# lcd.net
KiCad netlist of a schematic drawn in EAGLE
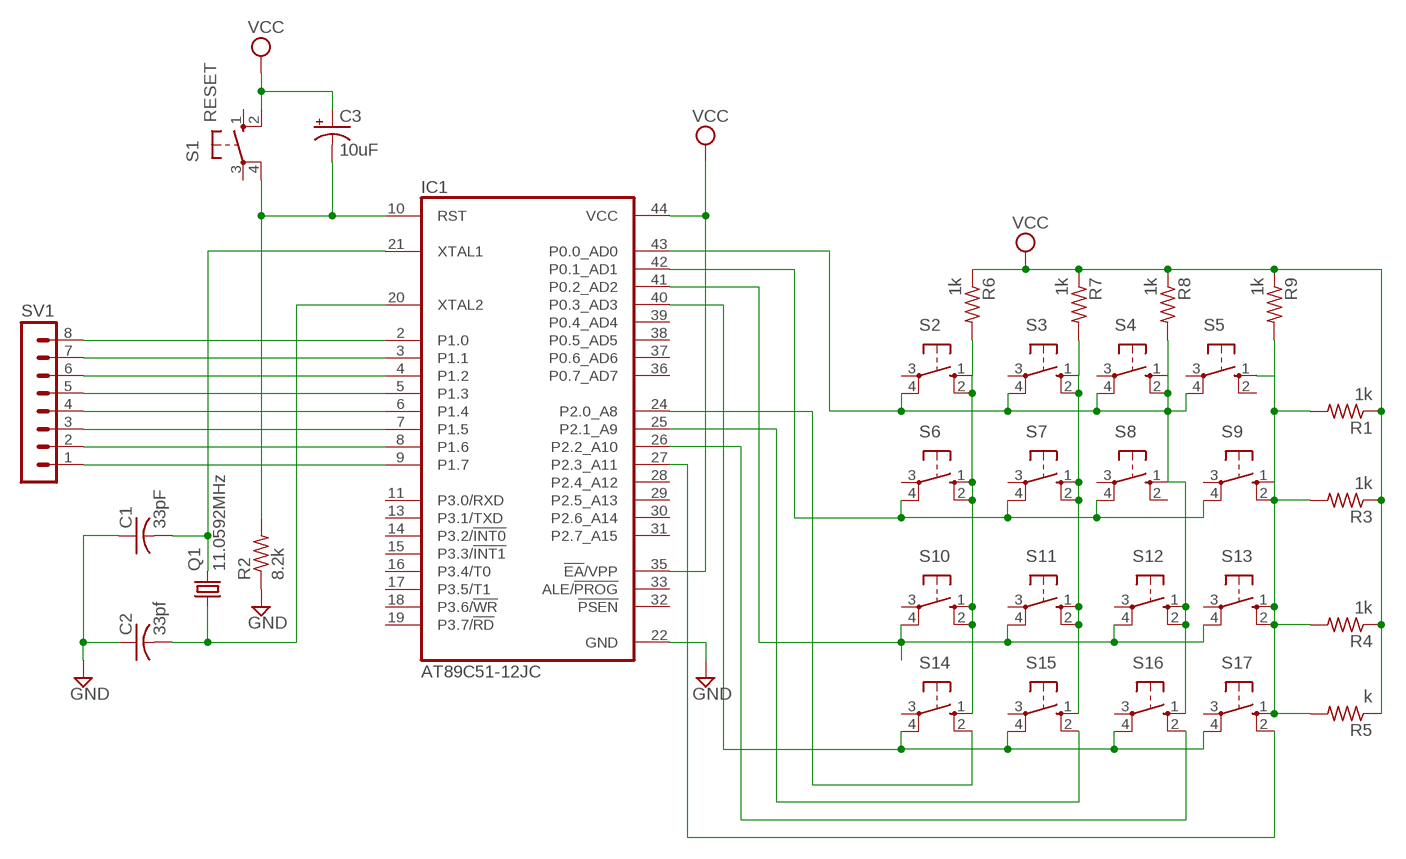
[diagram p0: schematic, sheet 1]

(export (version "E")
  (design (tool "Eeschema 10.0.6"))
  (components
    (comp (ref "C1")
      (value "33pF")
      (footprint "eagle-import:C025-025X050")
      (libsource (lib "eagle-import") (part "C-US025-025X050"))
    )
    (comp (ref "C2")
      (value "33pf")
      (footprint "eagle-import:C025-025X050")
      (libsource (lib "eagle-import") (part "C-US025-025X050"))
    )
    (comp (ref "C3")
      (value "10uF")
      (footprint "eagle-import:E2,5-5")
      (libsource (lib "eagle-import") (part "CPOL-USE2.5-5"))
    )
    (comp (ref "IC1")
      (value "AT89C51-12JC")
      (footprint "eagle-import:PLCC44")
      (fields (field (name "MPN") "AT89C51ED2-SLSUM"))
      (libsource (lib "eagle-import") (part "AT89C51-JC12"))
    )
    (comp (ref "Q1")
      (value "11.0592MHz")
      (footprint "eagle-import:TC26H")
      (libsource (lib "eagle-import") (part "CRYSTALTC26H"))
    )
    (comp (ref "R1")
      (value "1k")
      (footprint "eagle-import:R2512")
      (libsource (lib "eagle-import") (part "R-US_R2512"))
    )
    (comp (ref "R2")
      (value "8.2k")
      (footprint "eagle-import:R2512")
      (libsource (lib "eagle-import") (part "R-US_R2512"))
    )
    (comp (ref "R3")
      (value "1k")
      (footprint "eagle-import:R2512")
      (libsource (lib "eagle-import") (part "R-US_R2512"))
    )
    (comp (ref "R4")
      (value "1k")
      (footprint "eagle-import:R2512")
      (libsource (lib "eagle-import") (part "R-US_R2512"))
    )
    (comp (ref "R5")
      (value "k")
      (footprint "eagle-import:R2512")
      (libsource (lib "eagle-import") (part "R-US_R2512"))
    )
    (comp (ref "R6")
      (value "1k")
      (footprint "eagle-import:R2512")
      (libsource (lib "eagle-import") (part "R-US_R2512"))
    )
    (comp (ref "R7")
      (value "1k")
      (footprint "eagle-import:R2512")
      (libsource (lib "eagle-import") (part "R-US_R2512"))
    )
    (comp (ref "R8")
      (value "1k")
      (footprint "eagle-import:R2512")
      (libsource (lib "eagle-import") (part "R-US_R2512"))
    )
    (comp (ref "R9")
      (value "1k")
      (footprint "eagle-import:R2512")
      (libsource (lib "eagle-import") (part "R-US_R2512"))
    )
    (comp (ref "S1")
      (value "RESET")
      (footprint "eagle-import:B3F-10XX")
      (fields (field (name "MPN") "B3F-1000"))
      (libsource (lib "eagle-import") (part "10-XX"))
    )
    (comp (ref "S2")
      (value "10-XX")
      (footprint "eagle-import:B3F-10XX")
      (fields (field (name "MPN") "B3F-1000"))
      (libsource (lib "eagle-import") (part "10-XX"))
    )
    (comp (ref "S3")
      (value "10-XX")
      (footprint "eagle-import:B3F-10XX")
      (fields (field (name "MPN") "B3F-1000"))
      (libsource (lib "eagle-import") (part "10-XX"))
    )
    (comp (ref "S4")
      (value "10-XX")
      (footprint "eagle-import:B3F-10XX")
      (fields (field (name "MPN") "B3F-1000"))
      (libsource (lib "eagle-import") (part "10-XX"))
    )
    (comp (ref "S5")
      (value "10-XX")
      (footprint "eagle-import:B3F-10XX")
      (fields (field (name "MPN") "B3F-1000"))
      (libsource (lib "eagle-import") (part "10-XX"))
    )
    (comp (ref "S6")
      (value "10-XX")
      (footprint "eagle-import:B3F-10XX")
      (fields (field (name "MPN") "B3F-1000"))
      (libsource (lib "eagle-import") (part "10-XX"))
    )
    (comp (ref "S7")
      (value "10-XX")
      (footprint "eagle-import:B3F-10XX")
      (fields (field (name "MPN") "B3F-1000"))
      (libsource (lib "eagle-import") (part "10-XX"))
    )
    (comp (ref "S8")
      (value "10-XX")
      (footprint "eagle-import:B3F-10XX")
      (fields (field (name "MPN") "B3F-1000"))
      (libsource (lib "eagle-import") (part "10-XX"))
    )
    (comp (ref "S9")
      (value "10-XX")
      (footprint "eagle-import:B3F-10XX")
      (fields (field (name "MPN") "B3F-1000"))
      (libsource (lib "eagle-import") (part "10-XX"))
    )
    (comp (ref "S10")
      (value "10-XX")
      (footprint "eagle-import:B3F-10XX")
      (fields (field (name "MPN") "B3F-1000"))
      (libsource (lib "eagle-import") (part "10-XX"))
    )
    (comp (ref "S11")
      (value "10-XX")
      (footprint "eagle-import:B3F-10XX")
      (fields (field (name "MPN") "B3F-1000"))
      (libsource (lib "eagle-import") (part "10-XX"))
    )
    (comp (ref "S12")
      (value "10-XX")
      (footprint "eagle-import:B3F-10XX")
      (fields (field (name "MPN") "B3F-1000"))
      (libsource (lib "eagle-import") (part "10-XX"))
    )
    (comp (ref "S13")
      (value "10-XX")
      (footprint "eagle-import:B3F-10XX")
      (fields (field (name "MPN") "B3F-1000"))
      (libsource (lib "eagle-import") (part "10-XX"))
    )
    (comp (ref "S14")
      (value "10-XX")
      (footprint "eagle-import:B3F-10XX")
      (fields (field (name "MPN") "B3F-1000"))
      (libsource (lib "eagle-import") (part "10-XX"))
    )
    (comp (ref "S15")
      (value "10-XX")
      (footprint "eagle-import:B3F-10XX")
      (fields (field (name "MPN") "B3F-1000"))
      (libsource (lib "eagle-import") (part "10-XX"))
    )
    (comp (ref "S16")
      (value "10-XX")
      (footprint "eagle-import:B3F-10XX")
      (fields (field (name "MPN") "B3F-1000"))
      (libsource (lib "eagle-import") (part "10-XX"))
    )
    (comp (ref "S17")
      (value "10-XX")
      (footprint "eagle-import:B3F-10XX")
      (fields (field (name "MPN") "B3F-1000"))
      (libsource (lib "eagle-import") (part "10-XX"))
    )
    (comp (ref "SV1")
      (value "MA08-1W")
      (footprint "eagle-import:MA08-1W")
      (libsource (lib "eagle-import") (part "MA08-1W"))
    )
  )
  (nets
    (net (code "1") (name "GND") (class "Default")
      (node (ref "C1") (pin "1") (pinfunction "1_1") (pintype "passive"))
      (node (ref "C2") (pin "1") (pinfunction "1_1") (pintype "passive"))
      (node (ref "IC1") (pin "22") (pinfunction "GND_22") (pintype "power_in"))
      (node (ref "R2") (pin "1") (pinfunction "1_1") (pintype "passive"))
    )
    (net (code "2") (name "Net-(IC1-P0.0_AD0)") (class "Default")
      (node (ref "IC1") (pin "43") (pinfunction "P0.0_AD0_43") (pintype "bidirectional"))
      (node (ref "R8") (pin "2") (pinfunction "2_2") (pintype "passive"))
      (node (ref "S12") (pin "1") (pinfunction "S_1") (pintype "passive"))
      (node (ref "S12") (pin "2") (pinfunction "S1_2") (pintype "passive"))
      (node (ref "S16") (pin "1") (pinfunction "S_1") (pintype "passive"))
      (node (ref "S2") (pin "4") (pinfunction "P1_4") (pintype "passive"))
      (node (ref "S3") (pin "4") (pinfunction "P1_4") (pintype "passive"))
      (node (ref "S4") (pin "1") (pinfunction "S_1") (pintype "passive"))
      (node (ref "S4") (pin "2") (pinfunction "S1_2") (pintype "passive"))
      (node (ref "S4") (pin "4") (pinfunction "P1_4") (pintype "passive"))
      (node (ref "S5") (pin "4") (pinfunction "P1_4") (pintype "passive"))
      (node (ref "S8") (pin "1") (pinfunction "S_1") (pintype "passive"))
    )
    (net (code "3") (name "Net-(IC1-P0.1_AD1)") (class "Default")
      (node (ref "IC1") (pin "42") (pinfunction "P0.1_AD1_42") (pintype "bidirectional"))
      (node (ref "S6") (pin "4") (pinfunction "P1_4") (pintype "passive"))
      (node (ref "S7") (pin "4") (pinfunction "P1_4") (pintype "passive"))
      (node (ref "S8") (pin "4") (pinfunction "P1_4") (pintype "passive"))
      (node (ref "S9") (pin "4") (pinfunction "P1_4") (pintype "passive"))
    )
    (net (code "4") (name "Net-(IC1-P0.2_AD2)") (class "Default")
      (node (ref "IC1") (pin "41") (pinfunction "P0.2_AD2_41") (pintype "bidirectional"))
      (node (ref "S10") (pin "4") (pinfunction "P1_4") (pintype "passive"))
      (node (ref "S11") (pin "4") (pinfunction "P1_4") (pintype "passive"))
      (node (ref "S12") (pin "4") (pinfunction "P1_4") (pintype "passive"))
      (node (ref "S13") (pin "4") (pinfunction "P1_4") (pintype "passive"))
    )
    (net (code "5") (name "Net-(IC1-P0.3_AD3)") (class "Default")
      (node (ref "IC1") (pin "40") (pinfunction "P0.3_AD3_40") (pintype "bidirectional"))
      (node (ref "S14") (pin "4") (pinfunction "P1_4") (pintype "passive"))
      (node (ref "S15") (pin "4") (pinfunction "P1_4") (pintype "passive"))
      (node (ref "S16") (pin "4") (pinfunction "P1_4") (pintype "passive"))
      (node (ref "S17") (pin "4") (pinfunction "P1_4") (pintype "passive"))
    )
    (net (code "6") (name "Net-(IC1-P1.0)") (class "Default")
      (node (ref "IC1") (pin "2") (pinfunction "P1.0_2") (pintype "bidirectional"))
      (node (ref "SV1") (pin "8") (pinfunction "8_8") (pintype "passive"))
    )
    (net (code "7") (name "Net-(IC1-P1.1)") (class "Default")
      (node (ref "IC1") (pin "3") (pinfunction "P1.1_3") (pintype "bidirectional"))
      (node (ref "SV1") (pin "7") (pinfunction "7_7") (pintype "passive"))
    )
    (net (code "8") (name "Net-(IC1-P1.2)") (class "Default")
      (node (ref "IC1") (pin "4") (pinfunction "P1.2_4") (pintype "bidirectional"))
      (node (ref "SV1") (pin "6") (pinfunction "6_6") (pintype "passive"))
    )
    (net (code "9") (name "Net-(IC1-P1.3)") (class "Default")
      (node (ref "IC1") (pin "5") (pinfunction "P1.3_5") (pintype "bidirectional"))
      (node (ref "SV1") (pin "5") (pinfunction "5_5") (pintype "passive"))
    )
    (net (code "10") (name "Net-(IC1-P1.4)") (class "Default")
      (node (ref "IC1") (pin "6") (pinfunction "P1.4_6") (pintype "bidirectional"))
      (node (ref "SV1") (pin "4") (pinfunction "4_4") (pintype "passive"))
    )
    (net (code "11") (name "Net-(IC1-P1.5)") (class "Default")
      (node (ref "IC1") (pin "7") (pinfunction "P1.5_7") (pintype "bidirectional"))
      (node (ref "SV1") (pin "3") (pinfunction "3_3") (pintype "passive"))
    )
    (net (code "12") (name "Net-(IC1-P1.6)") (class "Default")
      (node (ref "IC1") (pin "8") (pinfunction "P1.6_8") (pintype "bidirectional"))
      (node (ref "SV1") (pin "2") (pinfunction "2_2") (pintype "passive"))
    )
    (net (code "13") (name "Net-(IC1-P1.7)") (class "Default")
      (node (ref "IC1") (pin "9") (pinfunction "P1.7_9") (pintype "bidirectional"))
      (node (ref "SV1") (pin "1") (pinfunction "1_1") (pintype "passive"))
    )
    (net (code "14") (name "Net-(IC1-P2.0_A8)") (class "Default")
      (node (ref "IC1") (pin "24") (pinfunction "P2.0_A8_24") (pintype "bidirectional"))
      (node (ref "S14") (pin "2") (pinfunction "S1_2") (pintype "passive"))
    )
    (net (code "15") (name "Net-(IC1-P2.1_A9)") (class "Default")
      (node (ref "IC1") (pin "25") (pinfunction "P2.1_A9_25") (pintype "bidirectional"))
      (node (ref "S15") (pin "2") (pinfunction "S1_2") (pintype "passive"))
    )
    (net (code "16") (name "Net-(IC1-P2.2_A10)") (class "Default")
      (node (ref "IC1") (pin "26") (pinfunction "P2.2_A10_26") (pintype "bidirectional"))
      (node (ref "S16") (pin "2") (pinfunction "S1_2") (pintype "passive"))
    )
    (net (code "17") (name "Net-(IC1-P2.3_A11)") (class "Default")
      (node (ref "IC1") (pin "27") (pinfunction "P2.3_A11_27") (pintype "bidirectional"))
      (node (ref "S17") (pin "2") (pinfunction "S1_2") (pintype "passive"))
    )
    (net (code "18") (name "Net-(IC1-RST)") (class "Default")
      (node (ref "C3") (pin "-") (pinfunction "-_-") (pintype "passive"))
      (node (ref "IC1") (pin "10") (pinfunction "RST_10") (pintype "input"))
      (node (ref "R2") (pin "2") (pinfunction "2_2") (pintype "passive"))
      (node (ref "S1") (pin "4") (pinfunction "P1_4") (pintype "passive"))
    )
    (net (code "19") (name "Net-(IC1-XTAL1)") (class "Default")
      (node (ref "C1") (pin "2") (pinfunction "2_2") (pintype "passive"))
      (node (ref "IC1") (pin "21") (pinfunction "XTAL1_21") (pintype "input"))
      (node (ref "Q1") (pin "2") (pinfunction "2_2") (pintype "passive"))
    )
    (net (code "20") (name "Net-(IC1-XTAL2)") (class "Default")
      (node (ref "C2") (pin "2") (pinfunction "2_2") (pintype "passive"))
      (node (ref "IC1") (pin "20") (pinfunction "XTAL2_20") (pintype "input"))
      (node (ref "Q1") (pin "1") (pinfunction "1_1") (pintype "passive"))
    )
    (net (code "21") (name "Net-(S10-S)") (class "Default")
      (node (ref "R6") (pin "2") (pinfunction "2_2") (pintype "passive"))
      (node (ref "S10") (pin "1") (pinfunction "S_1") (pintype "passive"))
      (node (ref "S10") (pin "2") (pinfunction "S1_2") (pintype "passive"))
      (node (ref "S14") (pin "1") (pinfunction "S_1") (pintype "passive"))
      (node (ref "S2") (pin "1") (pinfunction "S_1") (pintype "passive"))
      (node (ref "S2") (pin "2") (pinfunction "S1_2") (pintype "passive"))
      (node (ref "S6") (pin "1") (pinfunction "S_1") (pintype "passive"))
      (node (ref "S6") (pin "2") (pinfunction "S1_2") (pintype "passive"))
    )
    (net (code "22") (name "Net-(S11-S)") (class "Default")
      (node (ref "R7") (pin "2") (pinfunction "2_2") (pintype "passive"))
      (node (ref "S11") (pin "1") (pinfunction "S_1") (pintype "passive"))
      (node (ref "S11") (pin "2") (pinfunction "S1_2") (pintype "passive"))
      (node (ref "S15") (pin "1") (pinfunction "S_1") (pintype "passive"))
      (node (ref "S3") (pin "1") (pinfunction "S_1") (pintype "passive"))
      (node (ref "S3") (pin "2") (pinfunction "S1_2") (pintype "passive"))
      (node (ref "S7") (pin "1") (pinfunction "S_1") (pintype "passive"))
      (node (ref "S7") (pin "2") (pinfunction "S1_2") (pintype "passive"))
    )
    (net (code "23") (name "Net-(S13-S)") (class "Default")
      (node (ref "R1") (pin "2") (pinfunction "2_2") (pintype "passive"))
      (node (ref "R3") (pin "2") (pinfunction "2_2") (pintype "passive"))
      (node (ref "R4") (pin "2") (pinfunction "2_2") (pintype "passive"))
      (node (ref "R5") (pin "2") (pinfunction "2_2") (pintype "passive"))
      (node (ref "R9") (pin "2") (pinfunction "2_2") (pintype "passive"))
      (node (ref "S13") (pin "1") (pinfunction "S_1") (pintype "passive"))
      (node (ref "S13") (pin "2") (pinfunction "S1_2") (pintype "passive"))
      (node (ref "S17") (pin "1") (pinfunction "S_1") (pintype "passive"))
      (node (ref "S5") (pin "1") (pinfunction "S_1") (pintype "passive"))
      (node (ref "S9") (pin "1") (pinfunction "S_1") (pintype "passive"))
      (node (ref "S9") (pin "2") (pinfunction "S1_2") (pintype "passive"))
    )
    (net (code "24") (name "VCC") (class "Default")
      (node (ref "C3") (pin "+") (pinfunction "+_+") (pintype "passive"))
      (node (ref "IC1") (pin "35") (pinfunction "~{EA}/VPP_35") (pintype "input"))
      (node (ref "IC1") (pin "44") (pinfunction "VCC_44") (pintype "power_in"))
      (node (ref "R1") (pin "1") (pinfunction "1_1") (pintype "passive"))
      (node (ref "R3") (pin "1") (pinfunction "1_1") (pintype "passive"))
      (node (ref "R4") (pin "1") (pinfunction "1_1") (pintype "passive"))
      (node (ref "R5") (pin "1") (pinfunction "1_1") (pintype "passive"))
      (node (ref "R6") (pin "1") (pinfunction "1_1") (pintype "passive"))
      (node (ref "R7") (pin "1") (pinfunction "1_1") (pintype "passive"))
      (node (ref "R8") (pin "1") (pinfunction "1_1") (pintype "passive"))
      (node (ref "R9") (pin "1") (pinfunction "1_1") (pintype "passive"))
      (node (ref "S1") (pin "2") (pinfunction "S1_2") (pintype "passive"))
    )
    (net (code "25") (name "unconnected-(IC1-ALE{slash}~{PROG}-Pad33)") (class "Default")
      (node (ref "IC1") (pin "33") (pinfunction "ALE/~{PROG}_33") (pintype "output"))
    )
    (net (code "26") (name "unconnected-(IC1-P0.4_AD4-Pad39)") (class "Default")
      (node (ref "IC1") (pin "39") (pinfunction "P0.4_AD4_39") (pintype "bidirectional"))
    )
    (net (code "27") (name "unconnected-(IC1-P0.5_AD5-Pad38)") (class "Default")
      (node (ref "IC1") (pin "38") (pinfunction "P0.5_AD5_38") (pintype "bidirectional"))
    )
    (net (code "28") (name "unconnected-(IC1-P0.6_AD6-Pad37)") (class "Default")
      (node (ref "IC1") (pin "37") (pinfunction "P0.6_AD6_37") (pintype "bidirectional"))
    )
    (net (code "29") (name "unconnected-(IC1-P0.7_AD7-Pad36)") (class "Default")
      (node (ref "IC1") (pin "36") (pinfunction "P0.7_AD7_36") (pintype "bidirectional"))
    )
    (net (code "30") (name "unconnected-(IC1-P2.4_A12-Pad28)") (class "Default")
      (node (ref "IC1") (pin "28") (pinfunction "P2.4_A12_28") (pintype "bidirectional"))
    )
    (net (code "31") (name "unconnected-(IC1-P2.5_A13-Pad29)") (class "Default")
      (node (ref "IC1") (pin "29") (pinfunction "P2.5_A13_29") (pintype "bidirectional"))
    )
    (net (code "32") (name "unconnected-(IC1-P2.6_A14-Pad30)") (class "Default")
      (node (ref "IC1") (pin "30") (pinfunction "P2.6_A14_30") (pintype "bidirectional"))
    )
    (net (code "33") (name "unconnected-(IC1-P2.7_A15-Pad31)") (class "Default")
      (node (ref "IC1") (pin "31") (pinfunction "P2.7_A15_31") (pintype "bidirectional"))
    )
    (net (code "34") (name "unconnected-(IC1-P3.0{slash}RXD-Pad11)") (class "Default")
      (node (ref "IC1") (pin "11") (pinfunction "P3.0/RXD_11") (pintype "bidirectional"))
    )
    (net (code "35") (name "unconnected-(IC1-P3.1{slash}TXD-Pad13)") (class "Default")
      (node (ref "IC1") (pin "13") (pinfunction "P3.1/TXD_13") (pintype "bidirectional"))
    )
    (net (code "36") (name "unconnected-(IC1-P3.2{slash}~{INT0}-Pad14)") (class "Default")
      (node (ref "IC1") (pin "14") (pinfunction "P3.2/~{INT0}_14") (pintype "bidirectional"))
    )
    (net (code "37") (name "unconnected-(IC1-P3.3{slash}~{INT1}-Pad15)") (class "Default")
      (node (ref "IC1") (pin "15") (pinfunction "P3.3/~{INT1}_15") (pintype "bidirectional"))
    )
    (net (code "38") (name "unconnected-(IC1-P3.4{slash}T0-Pad16)") (class "Default")
      (node (ref "IC1") (pin "16") (pinfunction "P3.4/T0_16") (pintype "bidirectional"))
    )
    (net (code "39") (name "unconnected-(IC1-P3.5{slash}T1-Pad17)") (class "Default")
      (node (ref "IC1") (pin "17") (pinfunction "P3.5/T1_17") (pintype "bidirectional"))
    )
    (net (code "40") (name "unconnected-(IC1-P3.6{slash}~{WR}-Pad18)") (class "Default")
      (node (ref "IC1") (pin "18") (pinfunction "P3.6/~{WR}_18") (pintype "bidirectional"))
    )
    (net (code "41") (name "unconnected-(IC1-P3.7{slash}~{RD}-Pad19)") (class "Default")
      (node (ref "IC1") (pin "19") (pinfunction "P3.7/~{RD}_19") (pintype "bidirectional"))
    )
    (net (code "42") (name "unconnected-(IC1-~{PSEN}-Pad32)") (class "Default")
      (node (ref "IC1") (pin "32") (pinfunction "~{PSEN}_32") (pintype "output"))
    )
    (net (code "43") (name "unconnected-(S1-P-Pad3)") (class "Default")
      (node (ref "S1") (pin "3") (pinfunction "P_3") (pintype "passive"))
    )
    (net (code "44") (name "unconnected-(S1-S-Pad1)") (class "Default")
      (node (ref "S1") (pin "1") (pinfunction "S_1") (pintype "passive"))
    )
    (net (code "45") (name "unconnected-(S2-P-Pad3)") (class "Default")
      (node (ref "S2") (pin "3") (pinfunction "P_3") (pintype "passive"))
    )
    (net (code "46") (name "unconnected-(S3-P-Pad3)") (class "Default")
      (node (ref "S3") (pin "3") (pinfunction "P_3") (pintype "passive"))
    )
    (net (code "47") (name "unconnected-(S4-P-Pad3)") (class "Default")
      (node (ref "S4") (pin "3") (pinfunction "P_3") (pintype "passive"))
    )
    (net (code "48") (name "unconnected-(S5-P-Pad3)") (class "Default")
      (node (ref "S5") (pin "3") (pinfunction "P_3") (pintype "passive"))
    )
    (net (code "49") (name "unconnected-(S5-S1-Pad2)") (class "Default")
      (node (ref "S5") (pin "2") (pinfunction "S1_2") (pintype "passive"))
    )
    (net (code "50") (name "unconnected-(S6-P-Pad3)") (class "Default")
      (node (ref "S6") (pin "3") (pinfunction "P_3") (pintype "passive"))
    )
    (net (code "51") (name "unconnected-(S7-P-Pad3)") (class "Default")
      (node (ref "S7") (pin "3") (pinfunction "P_3") (pintype "passive"))
    )
    (net (code "52") (name "unconnected-(S8-P-Pad3)") (class "Default")
      (node (ref "S8") (pin "3") (pinfunction "P_3") (pintype "passive"))
    )
    (net (code "53") (name "unconnected-(S8-S1-Pad2)") (class "Default")
      (node (ref "S8") (pin "2") (pinfunction "S1_2") (pintype "passive"))
    )
    (net (code "54") (name "unconnected-(S9-P-Pad3)") (class "Default")
      (node (ref "S9") (pin "3") (pinfunction "P_3") (pintype "passive"))
    )
    (net (code "55") (name "unconnected-(S10-P-Pad3)") (class "Default")
      (node (ref "S10") (pin "3") (pinfunction "P_3") (pintype "passive"))
    )
    (net (code "56") (name "unconnected-(S11-P-Pad3)") (class "Default")
      (node (ref "S11") (pin "3") (pinfunction "P_3") (pintype "passive"))
    )
    (net (code "57") (name "unconnected-(S12-P-Pad3)") (class "Default")
      (node (ref "S12") (pin "3") (pinfunction "P_3") (pintype "passive"))
    )
    (net (code "58") (name "unconnected-(S13-P-Pad3)") (class "Default")
      (node (ref "S13") (pin "3") (pinfunction "P_3") (pintype "passive"))
    )
    (net (code "59") (name "unconnected-(S14-P-Pad3)") (class "Default")
      (node (ref "S14") (pin "3") (pinfunction "P_3") (pintype "passive"))
    )
    (net (code "60") (name "unconnected-(S15-P-Pad3)") (class "Default")
      (node (ref "S15") (pin "3") (pinfunction "P_3") (pintype "passive"))
    )
    (net (code "61") (name "unconnected-(S16-P-Pad3)") (class "Default")
      (node (ref "S16") (pin "3") (pinfunction "P_3") (pintype "passive"))
    )
    (net (code "62") (name "unconnected-(S17-P-Pad3)") (class "Default")
      (node (ref "S17") (pin "3") (pinfunction "P_3") (pintype "passive"))
    )
  )
)
